# rolladen.net
KiCad netlist of a schematic drawn in EAGLE
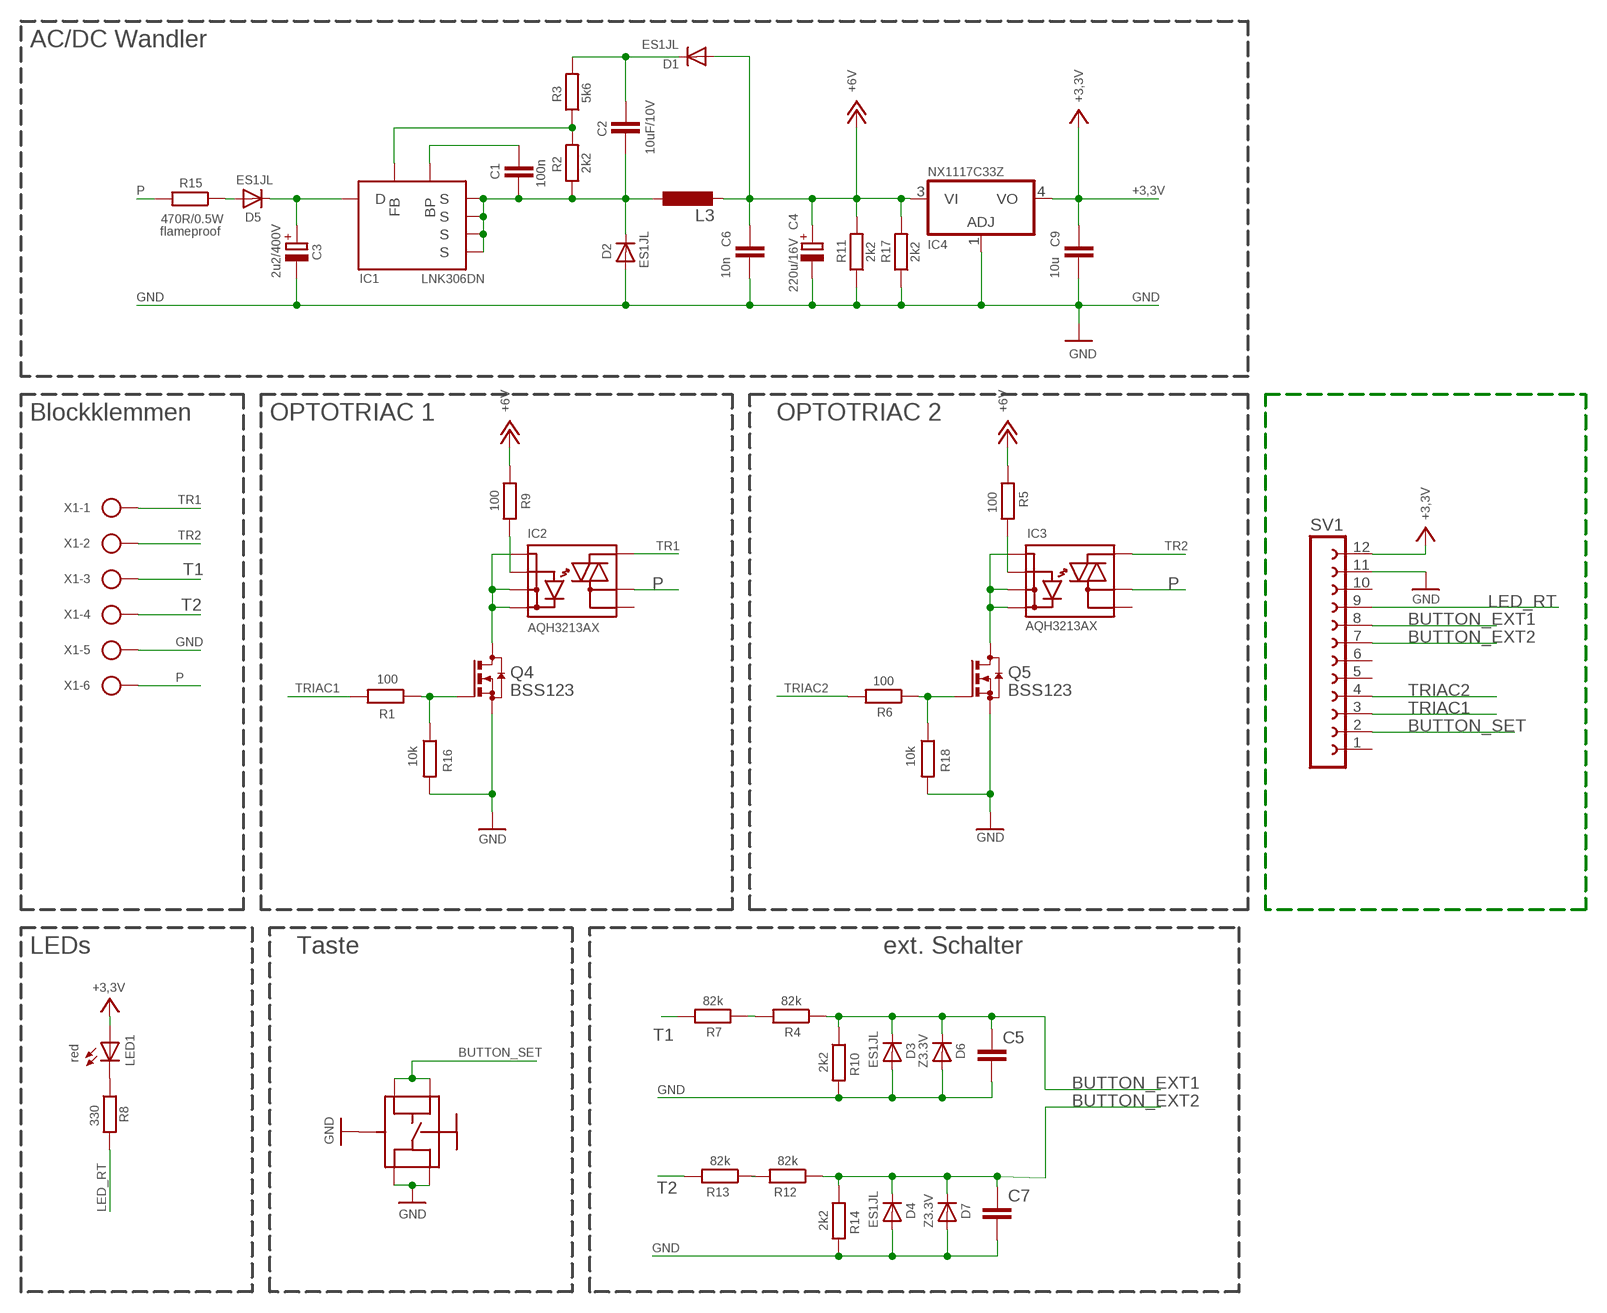
[diagram p0: schematic, sheet 1]

(export (version "E")
  (design (tool "Eeschema 10.0.6"))
  (components
    (comp (ref "C1")
      (value "100n")
      (footprint "eagle-import:C0603")
      (libsource (lib "eagle-import") (part "C-EUC0603"))
    )
    (comp (ref "C2")
      (value "10uF/10V")
      (footprint "eagle-import:C0805")
      (libsource (lib "eagle-import") (part "C-EUC0805"))
    )
    (comp (ref "C3")
      (value "2u2/400V")
      (footprint "eagle-import:TT5D11L")
      (libsource (lib "eagle-import") (part "CPOL-EUTT5D11L"))
    )
    (comp (ref "C4")
      (value "220u/16V")
      (footprint "eagle-import:153CLV-0605")
      (libsource (lib "eagle-import") (part "CPOL-EU153CLV-0605"))
    )
    (comp (ref "C5")
      (value "C-EUC0603")
      (footprint "eagle-import:C0603")
      (libsource (lib "eagle-import") (part "C-EUC0603"))
    )
    (comp (ref "C6")
      (value "10n")
      (footprint "eagle-import:C0603")
      (libsource (lib "eagle-import") (part "C-EUC0603"))
    )
    (comp (ref "C7")
      (value "C-EUC0603")
      (footprint "eagle-import:C0603")
      (libsource (lib "eagle-import") (part "C-EUC0603"))
    )
    (comp (ref "C9")
      (value "10u")
      (footprint "eagle-import:C0805")
      (libsource (lib "eagle-import") (part "C-EUC0805"))
    )
    (comp (ref "D1")
      (value "ES1JL")
      (footprint "eagle-import:SOD323-W")
      (libsource (lib "eagle-import") (part "DIODE-SOD323-W"))
    )
    (comp (ref "D2")
      (value "ES1JL")
      (footprint "eagle-import:SOD323-W")
      (libsource (lib "eagle-import") (part "DIODE-SOD323-W"))
    )
    (comp (ref "D3")
      (value "ES1JL")
      (footprint "eagle-import:SOD323-W")
      (libsource (lib "eagle-import") (part "DIODE-SOD323-W"))
    )
    (comp (ref "D4")
      (value "ES1JL")
      (footprint "eagle-import:SOD323-W")
      (libsource (lib "eagle-import") (part "DIODE-SOD323-W"))
    )
    (comp (ref "D5")
      (value "ES1JL")
      (footprint "eagle-import:SOD323-W")
      (libsource (lib "eagle-import") (part "DIODE-SOD323-W"))
    )
    (comp (ref "D6")
      (value "Z3.3V")
      (footprint "eagle-import:SOD323-W")
      (libsource (lib "eagle-import") (part "DIODE-SOD323-W"))
    )
    (comp (ref "D7")
      (value "Z3.3V")
      (footprint "eagle-import:SOD323-W")
      (libsource (lib "eagle-import") (part "DIODE-SOD323-W"))
    )
    (comp (ref "IC1")
      (value "LNK306DN")
      (footprint "eagle-import:SO-8C")
      (libsource (lib "eagle-import") (part "LNK306"))
    )
    (comp (ref "IC2")
      (value "AQH3213AX")
      (footprint "eagle-import:SO-08D")
      (libsource (lib "eagle-import") (part "AQHRELAYS"))
    )
    (comp (ref "IC3")
      (value "AQH3213AX")
      (footprint "eagle-import:SO-08D")
      (libsource (lib "eagle-import") (part "AQHRELAYS"))
    )
    (comp (ref "IC4")
      (value "NX1117C33Z")
      (footprint "eagle-import:SOT223")
      (libsource (lib "eagle-import") (part "317EMP"))
    )
    (comp (ref "L3")
      (value "L-EUWE-TPC")
      (footprint "eagle-import:POWER-CHOKE_WE-TPC")
      (libsource (lib "eagle-import") (part "L-EUWE-TPC"))
    )
    (comp (ref "LED1")
      (value "red")
      (footprint "eagle-import:CHIPLED_0603")
      (libsource (lib "eagle-import") (part "LEDCHIPLED_0603"))
    )
    (comp (ref "Q4")
      (value "BSS123")
      (footprint "eagle-import:SOT23")
      (libsource (lib "eagle-import") (part "BSS123"))
    )
    (comp (ref "Q5")
      (value "BSS123")
      (footprint "eagle-import:SOT23")
      (libsource (lib "eagle-import") (part "BSS123"))
    )
    (comp (ref "R1")
      (value "100")
      (footprint "eagle-import:R0603")
      (libsource (lib "eagle-import") (part "R-EU_R0603"))
    )
    (comp (ref "R2")
      (value "2k2")
      (footprint "eagle-import:R0603")
      (libsource (lib "eagle-import") (part "R-EU_R0603"))
    )
    (comp (ref "R3")
      (value "5k6")
      (footprint "eagle-import:R0603")
      (libsource (lib "eagle-import") (part "R-EU_R0603"))
    )
    (comp (ref "R4")
      (value "82k")
      (footprint "eagle-import:R0805")
      (libsource (lib "eagle-import") (part "R-EU_R0805"))
    )
    (comp (ref "R5")
      (value "100")
      (footprint "eagle-import:R0603")
      (libsource (lib "eagle-import") (part "R-EU_R0603"))
    )
    (comp (ref "R6")
      (value "100")
      (footprint "eagle-import:R0603")
      (libsource (lib "eagle-import") (part "R-EU_R0603"))
    )
    (comp (ref "R7")
      (value "82k")
      (footprint "eagle-import:R0805")
      (libsource (lib "eagle-import") (part "R-EU_R0805"))
    )
    (comp (ref "R8")
      (value "330")
      (footprint "eagle-import:R0603")
      (libsource (lib "eagle-import") (part "R-EU_R0603"))
    )
    (comp (ref "R9")
      (value "100")
      (footprint "eagle-import:R0603")
      (libsource (lib "eagle-import") (part "R-EU_R0603"))
    )
    (comp (ref "R10")
      (value "2k2")
      (footprint "eagle-import:R0603")
      (libsource (lib "eagle-import") (part "R-EU_R0603"))
    )
    (comp (ref "R11")
      (value "2k2")
      (footprint "eagle-import:R0603")
      (libsource (lib "eagle-import") (part "R-EU_R0603"))
    )
    (comp (ref "R12")
      (value "82k")
      (footprint "eagle-import:R0805")
      (libsource (lib "eagle-import") (part "R-EU_R0805"))
    )
    (comp (ref "R13")
      (value "82k")
      (footprint "eagle-import:R0805")
      (libsource (lib "eagle-import") (part "R-EU_R0805"))
    )
    (comp (ref "R14")
      (value "2k2")
      (footprint "eagle-import:R0603")
      (libsource (lib "eagle-import") (part "R-EU_R0603"))
    )
    (comp (ref "R15")
      (value "470R/0.5W")
      (footprint "eagle-import:0411V")
      (libsource (lib "eagle-import") (part "R-EU_0411/3V"))
    )
    (comp (ref "R16")
      (value "10k")
      (footprint "eagle-import:R0603")
      (libsource (lib "eagle-import") (part "R-EU_R0603"))
    )
    (comp (ref "R17")
      (value "2k2")
      (footprint "eagle-import:R0603")
      (libsource (lib "eagle-import") (part "R-EU_R0603"))
    )
    (comp (ref "R18")
      (value "10k")
      (footprint "eagle-import:R0603")
      (libsource (lib "eagle-import") (part "R-EU_R0603"))
    )
    (comp (ref "S1")
      (value "KMR")
      (footprint "eagle-import:KMR")
      (libsource (lib "eagle-import") (part "KMR"))
    )
    (comp (ref "SV1")
      (value "FE12-1")
      (footprint "eagle-import:FE12")
      (libsource (lib "eagle-import") (part "FE12-1"))
    )
    (comp (ref "X1")
      (value "W237-06P")
      (footprint "eagle-import:W237-6P")
      (libsource (lib "eagle-import") (part "W237-06P"))
    )
  )
  (nets
    (net (code "1") (name "+3,3V") (class "Default")
      (node (ref "C9") (pin "1") (pinfunction "1_1") (pintype "passive"))
      (node (ref "IC4") (pin "4") (pinfunction "VO_4") (pintype "passive"))
      (node (ref "LED1") (pin "A") (pinfunction "A_A") (pintype "passive"))
      (node (ref "SV1") (pin "12") (pinfunction "12_12") (pintype "passive"))
    )
    (net (code "2") (name "+6V") (class "Default")
      (node (ref "C4") (pin "+") (pinfunction "+_+") (pintype "passive"))
      (node (ref "C6") (pin "1") (pinfunction "1_1") (pintype "passive"))
      (node (ref "D1") (pin "A") (pinfunction "A_A") (pintype "passive"))
      (node (ref "IC4") (pin "3") (pinfunction "VI_3") (pintype "input"))
      (node (ref "L3") (pin "2") (pinfunction "2_2") (pintype "passive"))
      (node (ref "R11") (pin "2") (pinfunction "2_2") (pintype "passive"))
      (node (ref "R17") (pin "2") (pinfunction "2_2") (pintype "passive"))
      (node (ref "R5") (pin "1") (pinfunction "1_1") (pintype "passive"))
      (node (ref "R9") (pin "1") (pinfunction "1_1") (pintype "passive"))
    )
    (net (code "3") (name "/BUTTON_EXT1") (class "Default")
      (node (ref "C5") (pin "1") (pinfunction "1_1") (pintype "passive"))
      (node (ref "D3") (pin "C") (pinfunction "C_C") (pintype "passive"))
      (node (ref "D6") (pin "C") (pinfunction "C_C") (pintype "passive"))
      (node (ref "R10") (pin "1") (pinfunction "1_1") (pintype "passive"))
      (node (ref "R4") (pin "1") (pinfunction "1_1") (pintype "passive"))
      (node (ref "SV1") (pin "8") (pinfunction "8_8") (pintype "passive"))
    )
    (net (code "4") (name "/BUTTON_EXT2") (class "Default")
      (node (ref "C7") (pin "1") (pinfunction "1_1") (pintype "passive"))
      (node (ref "D4") (pin "C") (pinfunction "C_C") (pintype "passive"))
      (node (ref "D7") (pin "C") (pinfunction "C_C") (pintype "passive"))
      (node (ref "R12") (pin "1") (pinfunction "1_1") (pintype "passive"))
      (node (ref "R14") (pin "1") (pinfunction "1_1") (pintype "passive"))
      (node (ref "SV1") (pin "7") (pinfunction "7_7") (pintype "passive"))
    )
    (net (code "5") (name "/BUTTON_SET") (class "Default")
      (node (ref "S1") (pin "P$2") (pinfunction "P$2_P$2") (pintype "bidirectional"))
      (node (ref "S1") (pin "P$3") (pinfunction "P$3_P$3") (pintype "bidirectional"))
      (node (ref "SV1") (pin "2") (pinfunction "2_2") (pintype "passive"))
    )
    (net (code "6") (name "/LED_RT") (class "Default")
      (node (ref "R8") (pin "2") (pinfunction "2_2") (pintype "passive"))
      (node (ref "SV1") (pin "9") (pinfunction "9_9") (pintype "passive"))
    )
    (net (code "7") (name "/P") (class "Default")
      (node (ref "IC2") (pin "P$6") (pinfunction "P$6_P$6") (pintype "bidirectional"))
      (node (ref "IC3") (pin "P$6") (pinfunction "P$6_P$6") (pintype "bidirectional"))
      (node (ref "R15") (pin "2") (pinfunction "2_2") (pintype "passive"))
      (node (ref "X1") (pin "6") (pinfunction "KL_6") (pintype "passive"))
    )
    (net (code "8") (name "/T1") (class "Default")
      (node (ref "R7") (pin "2") (pinfunction "2_2") (pintype "passive"))
      (node (ref "X1") (pin "3") (pinfunction "KL_3") (pintype "passive"))
    )
    (net (code "9") (name "/T2") (class "Default")
      (node (ref "R13") (pin "2") (pinfunction "2_2") (pintype "passive"))
      (node (ref "X1") (pin "4") (pinfunction "KL_4") (pintype "passive"))
    )
    (net (code "10") (name "/TR1") (class "Default")
      (node (ref "IC2") (pin "P$7") (pinfunction "P$7_P$7") (pintype "bidirectional"))
      (node (ref "X1") (pin "1") (pinfunction "KL_1") (pintype "passive"))
    )
    (net (code "11") (name "/TR2") (class "Default")
      (node (ref "IC3") (pin "P$7") (pinfunction "P$7_P$7") (pintype "bidirectional"))
      (node (ref "X1") (pin "2") (pinfunction "KL_2") (pintype "passive"))
    )
    (net (code "12") (name "/TRIAC1") (class "Default")
      (node (ref "R1") (pin "2") (pinfunction "2_2") (pintype "passive"))
      (node (ref "SV1") (pin "3") (pinfunction "3_3") (pintype "passive"))
    )
    (net (code "13") (name "/TRIAC2") (class "Default")
      (node (ref "R6") (pin "2") (pinfunction "2_2") (pintype "passive"))
      (node (ref "SV1") (pin "4") (pinfunction "4_4") (pintype "passive"))
    )
    (net (code "14") (name "GND") (class "Default")
      (node (ref "C3") (pin "-") (pinfunction "-_-") (pintype "passive"))
      (node (ref "C4") (pin "-") (pinfunction "-_-") (pintype "passive"))
      (node (ref "C5") (pin "2") (pinfunction "2_2") (pintype "passive"))
      (node (ref "C6") (pin "2") (pinfunction "2_2") (pintype "passive"))
      (node (ref "C7") (pin "2") (pinfunction "2_2") (pintype "passive"))
      (node (ref "C9") (pin "2") (pinfunction "2_2") (pintype "passive"))
      (node (ref "D2") (pin "A") (pinfunction "A_A") (pintype "passive"))
      (node (ref "D3") (pin "A") (pinfunction "A_A") (pintype "passive"))
      (node (ref "D4") (pin "A") (pinfunction "A_A") (pintype "passive"))
      (node (ref "D6") (pin "A") (pinfunction "A_A") (pintype "passive"))
      (node (ref "D7") (pin "A") (pinfunction "A_A") (pintype "passive"))
      (node (ref "IC4") (pin "1") (pinfunction "ADJ_1") (pintype "input"))
      (node (ref "Q4") (pin "2") (pinfunction "S_2") (pintype "passive"))
      (node (ref "Q5") (pin "2") (pinfunction "S_2") (pintype "passive"))
      (node (ref "R10") (pin "2") (pinfunction "2_2") (pintype "passive"))
      (node (ref "R11") (pin "1") (pinfunction "1_1") (pintype "passive"))
      (node (ref "R14") (pin "2") (pinfunction "2_2") (pintype "passive"))
      (node (ref "R16") (pin "2") (pinfunction "2_2") (pintype "passive"))
      (node (ref "R17") (pin "1") (pinfunction "1_1") (pintype "passive"))
      (node (ref "R18") (pin "2") (pinfunction "2_2") (pintype "passive"))
      (node (ref "S1") (pin "P$1") (pinfunction "P$1_P$1") (pintype "bidirectional"))
      (node (ref "S1") (pin "P$4") (pinfunction "P$4_P$4") (pintype "bidirectional"))
      (node (ref "S1") (pin "P$5") (pinfunction "P$5_P$5") (pintype "bidirectional"))
      (node (ref "SV1") (pin "11") (pinfunction "11_11") (pintype "passive"))
      (node (ref "X1") (pin "5") (pinfunction "KL_5") (pintype "passive"))
    )
    (net (code "15") (name "Net-(C1-Pad2)") (class "Default")
      (node (ref "C1") (pin "2") (pinfunction "2_2") (pintype "passive"))
      (node (ref "C2") (pin "2") (pinfunction "2_2") (pintype "passive"))
      (node (ref "D2") (pin "C") (pinfunction "C_C") (pintype "passive"))
      (node (ref "IC1") (pin "P$4") (pinfunction "S_P$4") (pintype "bidirectional"))
      (node (ref "IC1") (pin "P$5") (pinfunction "S_P$5") (pintype "bidirectional"))
      (node (ref "IC1") (pin "P$6") (pinfunction "S_P$6") (pintype "bidirectional"))
      (node (ref "IC1") (pin "P$7") (pinfunction "S_P$7") (pintype "bidirectional"))
      (node (ref "L3") (pin "1") (pinfunction "1_1") (pintype "passive"))
      (node (ref "R2") (pin "1") (pinfunction "1_1") (pintype "passive"))
    )
    (net (code "16") (name "Net-(C2-Pad1)") (class "Default")
      (node (ref "C2") (pin "1") (pinfunction "1_1") (pintype "passive"))
      (node (ref "D1") (pin "C") (pinfunction "C_C") (pintype "passive"))
      (node (ref "R3") (pin "2") (pinfunction "2_2") (pintype "passive"))
    )
    (net (code "17") (name "Net-(D5-PadA)") (class "Default")
      (node (ref "D5") (pin "A") (pinfunction "A_A") (pintype "passive"))
      (node (ref "R15") (pin "1") (pinfunction "1_1") (pintype "passive"))
    )
    (net (code "18") (name "Net-(IC1-BP)") (class "Default")
      (node (ref "C1") (pin "1") (pinfunction "1_1") (pintype "passive"))
      (node (ref "IC1") (pin "P$1") (pinfunction "BP_P$1") (pintype "bidirectional"))
    )
    (net (code "19") (name "Net-(IC1-D)") (class "Default")
      (node (ref "C3") (pin "+") (pinfunction "+_+") (pintype "passive"))
      (node (ref "D5") (pin "C") (pinfunction "C_C") (pintype "passive"))
      (node (ref "IC1") (pin "P$3") (pinfunction "D_P$3") (pintype "bidirectional"))
    )
    (net (code "20") (name "Net-(IC1-FB)") (class "Default")
      (node (ref "IC1") (pin "P$2") (pinfunction "FB_P$2") (pintype "bidirectional"))
      (node (ref "R2") (pin "2") (pinfunction "2_2") (pintype "passive"))
      (node (ref "R3") (pin "1") (pinfunction "1_1") (pintype "passive"))
    )
    (net (code "21") (name "Net-(IC2-PadP$2)") (class "Default")
      (node (ref "IC2") (pin "P$2") (pinfunction "P$2_P$2") (pintype "bidirectional"))
      (node (ref "R9") (pin "2") (pinfunction "2_2") (pintype "passive"))
    )
    (net (code "22") (name "Net-(IC3-PadP$2)") (class "Default")
      (node (ref "IC3") (pin "P$2") (pinfunction "P$2_P$2") (pintype "bidirectional"))
      (node (ref "R5") (pin "2") (pinfunction "2_2") (pintype "passive"))
    )
    (net (code "23") (name "Net-(LED1-PadC)") (class "Default")
      (node (ref "LED1") (pin "C") (pinfunction "C_C") (pintype "passive"))
      (node (ref "R8") (pin "1") (pinfunction "1_1") (pintype "passive"))
    )
    (net (code "24") (name "Net-(Q4-D)") (class "Default")
      (node (ref "IC2") (pin "P$1") (pinfunction "P$1_P$1") (pintype "bidirectional"))
      (node (ref "IC2") (pin "P$3") (pinfunction "P$3_P$3") (pintype "bidirectional"))
      (node (ref "IC2") (pin "P$4") (pinfunction "P$4_P$4") (pintype "bidirectional"))
      (node (ref "Q4") (pin "3") (pinfunction "D_3") (pintype "passive"))
    )
    (net (code "25") (name "Net-(Q4-G)") (class "Default")
      (node (ref "Q4") (pin "1") (pinfunction "G_1") (pintype "passive"))
      (node (ref "R1") (pin "1") (pinfunction "1_1") (pintype "passive"))
      (node (ref "R16") (pin "1") (pinfunction "1_1") (pintype "passive"))
    )
    (net (code "26") (name "Net-(Q5-D)") (class "Default")
      (node (ref "IC3") (pin "P$1") (pinfunction "P$1_P$1") (pintype "bidirectional"))
      (node (ref "IC3") (pin "P$3") (pinfunction "P$3_P$3") (pintype "bidirectional"))
      (node (ref "IC3") (pin "P$4") (pinfunction "P$4_P$4") (pintype "bidirectional"))
      (node (ref "Q5") (pin "3") (pinfunction "D_3") (pintype "passive"))
    )
    (net (code "27") (name "Net-(Q5-G)") (class "Default")
      (node (ref "Q5") (pin "1") (pinfunction "G_1") (pintype "passive"))
      (node (ref "R18") (pin "1") (pinfunction "1_1") (pintype "passive"))
      (node (ref "R6") (pin "1") (pinfunction "1_1") (pintype "passive"))
    )
    (net (code "28") (name "Net-(R4-Pad2)") (class "Default")
      (node (ref "R4") (pin "2") (pinfunction "2_2") (pintype "passive"))
      (node (ref "R7") (pin "1") (pinfunction "1_1") (pintype "passive"))
    )
    (net (code "29") (name "Net-(R12-Pad2)") (class "Default")
      (node (ref "R12") (pin "2") (pinfunction "2_2") (pintype "passive"))
      (node (ref "R13") (pin "1") (pinfunction "1_1") (pintype "passive"))
    )
    (net (code "30") (name "unconnected-(IC2-PadP$5)") (class "Default")
      (node (ref "IC2") (pin "P$5") (pinfunction "P$5_P$5") (pintype "bidirectional"))
    )
    (net (code "31") (name "unconnected-(IC3-PadP$5)") (class "Default")
      (node (ref "IC3") (pin "P$5") (pinfunction "P$5_P$5") (pintype "bidirectional"))
    )
    (net (code "32") (name "unconnected-(SV1-Pad1)") (class "Default")
      (node (ref "SV1") (pin "1") (pinfunction "1_1") (pintype "passive"))
    )
    (net (code "33") (name "unconnected-(SV1-Pad5)") (class "Default")
      (node (ref "SV1") (pin "5") (pinfunction "5_5") (pintype "passive"))
    )
    (net (code "34") (name "unconnected-(SV1-Pad6)") (class "Default")
      (node (ref "SV1") (pin "6") (pinfunction "6_6") (pintype "passive"))
    )
    (net (code "35") (name "unconnected-(SV1-Pad10)") (class "Default")
      (node (ref "SV1") (pin "10") (pinfunction "10_10") (pintype "passive"))
    )
  )
)
